# BusBoard.net
KiCad netlist of a schematic drawn in EAGLE
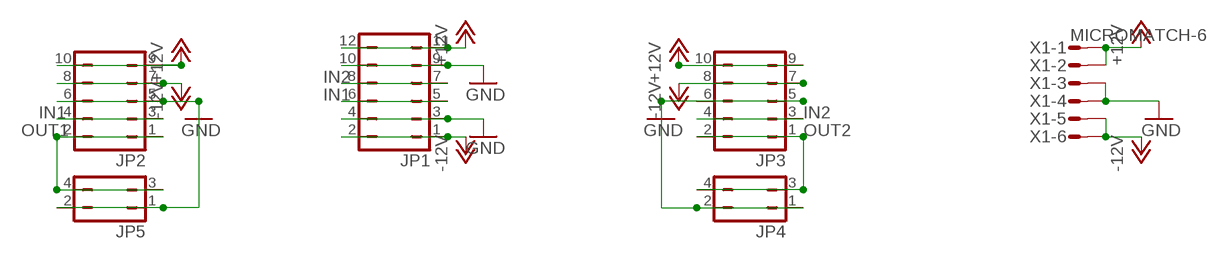
[diagram p0: schematic, sheet 1]

(export (version "E")
  (design (tool "Eeschema 10.0.6"))
  (components
    (comp (ref "JP1")
      (value "JP6Q")
      (footprint "eagle-import:JP6Q")
      (libsource (lib "eagle-import") (part "JP6Q"))
    )
    (comp (ref "JP2")
      (value "JP5Q")
      (footprint "eagle-import:JP5Q")
      (libsource (lib "eagle-import") (part "JP5Q"))
    )
    (comp (ref "JP3")
      (value "JP5Q")
      (footprint "eagle-import:JP5Q")
      (libsource (lib "eagle-import") (part "JP5Q"))
    )
    (comp (ref "JP4")
      (value "JP2Q")
      (footprint "eagle-import:JP2Q")
      (libsource (lib "eagle-import") (part "JP2Q"))
    )
    (comp (ref "JP5")
      (value "JP2Q")
      (footprint "eagle-import:JP2Q")
      (libsource (lib "eagle-import") (part "JP2Q"))
    )
    (comp (ref "X1")
      (value "MICROMATCH-6")
      (footprint "eagle-import:MICROMATCH-6")
      (fields (field (name "MPN") "7-215464-6"))
      (libsource (lib "eagle-import") (part "MICROMATCH-6"))
    )
  )
  (nets
    (net (code "1") (name "+12V") (class "Default")
      (node (ref "JP1") (pin "11") (pinfunction "11_11") (pintype "passive"))
      (node (ref "JP1") (pin "12") (pinfunction "12_12") (pintype "passive"))
      (node (ref "JP2") (pin "10") (pinfunction "10_10") (pintype "passive"))
      (node (ref "JP2") (pin "9") (pinfunction "9_9") (pintype "passive"))
      (node (ref "JP3") (pin "10") (pinfunction "10_10") (pintype "passive"))
      (node (ref "JP3") (pin "9") (pinfunction "9_9") (pintype "passive"))
      (node (ref "X1") (pin "1") (pinfunction "S_1") (pintype "passive"))
      (node (ref "X1") (pin "2") (pinfunction "S_2") (pintype "passive"))
    )
    (net (code "2") (name "-12V") (class "Default")
      (node (ref "JP1") (pin "1") (pinfunction "1_1") (pintype "passive"))
      (node (ref "JP1") (pin "2") (pinfunction "2_2") (pintype "passive"))
      (node (ref "JP2") (pin "7") (pinfunction "7_7") (pintype "passive"))
      (node (ref "JP2") (pin "8") (pinfunction "8_8") (pintype "passive"))
      (node (ref "JP3") (pin "7") (pinfunction "7_7") (pintype "passive"))
      (node (ref "JP3") (pin "8") (pinfunction "8_8") (pintype "passive"))
      (node (ref "X1") (pin "5") (pinfunction "S_5") (pintype "passive"))
      (node (ref "X1") (pin "6") (pinfunction "S_6") (pintype "passive"))
    )
    (net (code "3") (name "/IN1") (class "Default")
      (node (ref "JP1") (pin "5") (pinfunction "5_5") (pintype "passive"))
      (node (ref "JP1") (pin "6") (pinfunction "6_6") (pintype "passive"))
      (node (ref "JP2") (pin "3") (pinfunction "3_3") (pintype "passive"))
      (node (ref "JP2") (pin "4") (pinfunction "4_4") (pintype "passive"))
    )
    (net (code "4") (name "/IN2") (class "Default")
      (node (ref "JP1") (pin "7") (pinfunction "7_7") (pintype "passive"))
      (node (ref "JP1") (pin "8") (pinfunction "8_8") (pintype "passive"))
      (node (ref "JP3") (pin "3") (pinfunction "3_3") (pintype "passive"))
      (node (ref "JP3") (pin "4") (pinfunction "4_4") (pintype "passive"))
    )
    (net (code "5") (name "/OUT1") (class "Default")
      (node (ref "JP2") (pin "1") (pinfunction "1_1") (pintype "passive"))
      (node (ref "JP2") (pin "2") (pinfunction "2_2") (pintype "passive"))
      (node (ref "JP5") (pin "3") (pinfunction "3_3") (pintype "passive"))
      (node (ref "JP5") (pin "4") (pinfunction "4_4") (pintype "passive"))
    )
    (net (code "6") (name "/OUT2") (class "Default")
      (node (ref "JP3") (pin "1") (pinfunction "1_1") (pintype "passive"))
      (node (ref "JP3") (pin "2") (pinfunction "2_2") (pintype "passive"))
      (node (ref "JP4") (pin "3") (pinfunction "3_3") (pintype "passive"))
      (node (ref "JP4") (pin "4") (pinfunction "4_4") (pintype "passive"))
    )
    (net (code "7") (name "GND") (class "Default")
      (node (ref "JP1") (pin "10") (pinfunction "10_10") (pintype "passive"))
      (node (ref "JP1") (pin "3") (pinfunction "3_3") (pintype "passive"))
      (node (ref "JP1") (pin "4") (pinfunction "4_4") (pintype "passive"))
      (node (ref "JP1") (pin "9") (pinfunction "9_9") (pintype "passive"))
      (node (ref "JP2") (pin "5") (pinfunction "5_5") (pintype "passive"))
      (node (ref "JP2") (pin "6") (pinfunction "6_6") (pintype "passive"))
      (node (ref "JP3") (pin "5") (pinfunction "5_5") (pintype "passive"))
      (node (ref "JP3") (pin "6") (pinfunction "6_6") (pintype "passive"))
      (node (ref "JP4") (pin "1") (pinfunction "1_1") (pintype "passive"))
      (node (ref "JP4") (pin "2") (pinfunction "2_2") (pintype "passive"))
      (node (ref "JP5") (pin "1") (pinfunction "1_1") (pintype "passive"))
      (node (ref "JP5") (pin "2") (pinfunction "2_2") (pintype "passive"))
      (node (ref "X1") (pin "3") (pinfunction "S_3") (pintype "passive"))
      (node (ref "X1") (pin "4") (pinfunction "S_4") (pintype "passive"))
    )
  )
)
